# RADIO.net
KiCad netlist of a schematic drawn in Altium Designer
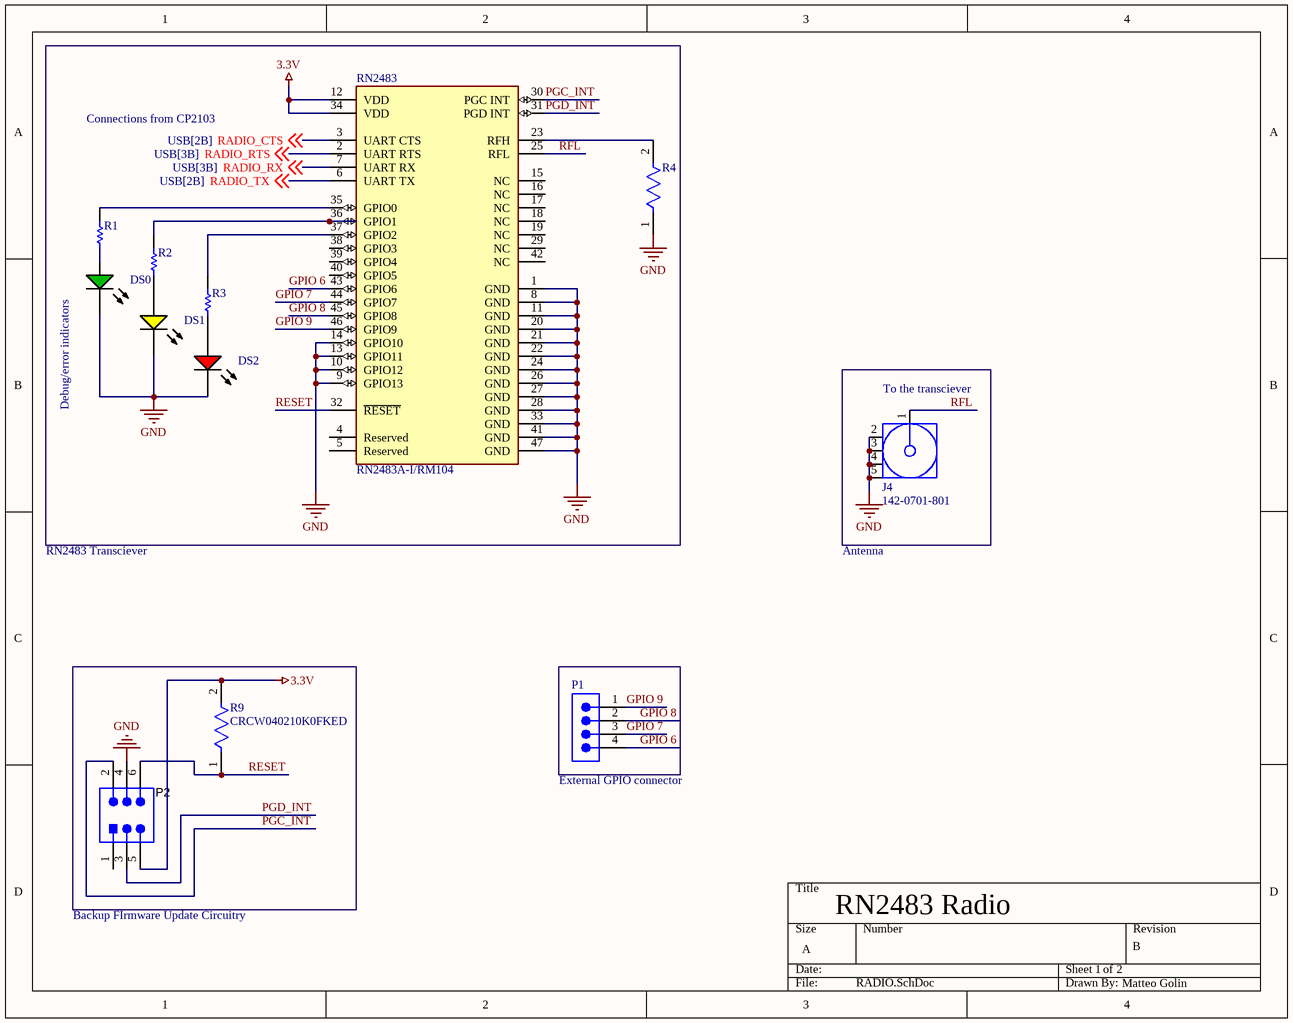
[diagram p0: RADIO.SchDoc]

(export (version "E")
  (design (tool "Eeschema 10.0.6"))
  (components
    (comp (ref "DS0")
      (value "HSMG-C190")
      (footprint "AVAG-HSMX-C190_V")
      (description "Chip LED, Green, 2.2 V, -40 to 85 degC, 2-Pin SMD, RoHS, Tape and Reel")
      (libsource (lib "Altium Content Vault") (part "LED-GREEN-AK-2"))
    )
    (comp (ref "DS1")
      (value "HSMY-C190")
      (footprint "AVAG-HSMX-C190_V")
      (description "LED Uni-Color Yellow, 65 mW, 20 mA, -40 to 85 degC, 2-Pin SMD, RoHS, Tape and Reel")
      (fields (field (name "TOLERANCE") "1%"))
      (libsource (lib "Altium Content Vault") (part "LED-YELLOW-AK-2"))
    )
    (comp (ref "DS2")
      (value "HSMH-C190")
      (footprint "AVAG-HSMX-C190_V")
      (description "LED Uni-Color Red, 65 mW, 20 mA, -40 to 85 degC, 2-Pin SMD, RoHS, Tape and Reel")
      (libsource (lib "Altium Content Vault") (part "LED-RED-AK-2"))
    )
    (comp (ref "J4")
      (value "142-0701-801")
      (footprint "CINC-142-0701-801_V")
      (description "SMA End Launch Jack Receptacle, 50 Ohm, 0 to 18 GHz, -65 to 165 degC, 5-Pin SMD, RoHS, Bulk")
      (fields (field (name "MANUFACTURER") "EmersonConnectivitySolutions"))
      (libsource (lib "Altium Content Vault") (part "CN-S-4F-RF5"))
    )
    (comp (ref "P1")
      (value "TSW-104-08-G-S")
      (footprint "SMTC-TSW-104-08-X-S")
      (description "0.025\" SQ Post Header, Through-hole, Vertical, -55 to 125 degC, 2.54 mm Pitch, 4-Pin, Male, RoHS")
      (fields (field (name "MANUFACTURER") "Samtec"))
      (libsource (lib "Altium Content Vault") (part "SMTC-TSW-104-08-X-S"))
    )
    (comp (ref "P2")
      (value "TSW-103-07-G-D")
      (footprint "SMTC-TSW-103-07-G-D_V")
      (fields (field (name "MANUFACTURER") "Samtec-Inc."))
      (libsource (lib "Altium Content Vault") (part "CN-2P-M-R6"))
    )
    (comp (ref "R1")
      (value "CRCW0402220KFKED")
      (footprint "RESC1005X40X25LL05T05")
      (fields (field (name "MANUFACTURER") "Vishay Dale"))
      (libsource (lib "Altium Content Vault") (part "RES"))
    )
    (comp (ref "R2")
      (value "CRCW0402220KFKED")
      (footprint "RESC1005X40X25LL05T05")
      (fields (field (name "MANUFACTURER") "Vishay Dale"))
      (libsource (lib "Altium Content Vault") (part "RES"))
    )
    (comp (ref "R3")
      (value "CRCW0402220KFKED")
      (footprint "RESC1005X40X25LL05T05")
      (fields (field (name "MANUFACTURER") "Vishay Dale"))
      (libsource (lib "Altium Content Vault") (part "RES"))
    )
    (comp (ref "R4")
      (value "CRCW060350R0FKEA")
      (footprint "FP-CRCW0603-e3-MFG")
      (description "RES Thick Film, 50Ω, 1%, 0.1W, 100ppm/°C, 0603")
      (fields (field (name "TOLERANCE") "1%"))
      (libsource (lib "Altium Content Vault") (part "1029c3af85768c4190bb7ad29bc67b5"))
    )
    (comp (ref "R9")
      (value "CRCW040210K0FKED")
      (footprint "FP-CRCW0402-e3-IPC_B")
      (description "RES SMD 10K OHM 1% 1/16W 0402")
      (fields (field (name "TOLERANCE") "1%"))
      (libsource (lib "Altium Content Vault") (part "1029c3af85768c4190bb7ad29bc67b5"))
    )
    (comp (ref "RN2483")
      (value "RN2483A-I/RM104")
      (footprint "FP-RN2483A-I-RM104-MFG")
      (fields
        (field (name "OCTOPART") "https://octopart.com/rn2483a-i%2Frm104-microchip-90584481")
        (field (name "MANUFACTURER") "Microchip")
      )
      (libsource (lib "Altium Content Vault") (part "630a5bff3a952dd521c0edb04079da7"))
    )
  )
  (nets
    (net (code "1") (name "/GPIO 6") (class "Default")
      (node (ref "P1") (pin "4") (pinfunction "4_4") (pintype "passive"))
      (node (ref "RN2483") (pin "43") (pinfunction "GPIO6_43") (pintype "bidirectional"))
    )
    (net (code "2") (name "/GPIO 7") (class "Default")
      (node (ref "P1") (pin "3") (pinfunction "3_3") (pintype "passive"))
      (node (ref "RN2483") (pin "44") (pinfunction "GPIO7_44") (pintype "bidirectional"))
    )
    (net (code "3") (name "/GPIO 8") (class "Default")
      (node (ref "P1") (pin "2") (pinfunction "2_2") (pintype "passive"))
      (node (ref "RN2483") (pin "45") (pinfunction "GPIO8_45") (pintype "bidirectional"))
    )
    (net (code "4") (name "/GPIO 9") (class "Default")
      (node (ref "P1") (pin "1") (pinfunction "1_1") (pintype "passive"))
      (node (ref "RN2483") (pin "46") (pinfunction "GPIO9_46") (pintype "bidirectional"))
    )
    (net (code "5") (name "/PGC_INT") (class "Default")
      (node (ref "P2") (pin "2") (pinfunction "2_2") (pintype "passive"))
      (node (ref "RN2483") (pin "30") (pinfunction "PGC_INT_30") (pintype "bidirectional"))
    )
    (net (code "6") (name "/PGD_INT") (class "Default")
      (node (ref "P2") (pin "3") (pinfunction "3_3") (pintype "passive"))
      (node (ref "RN2483") (pin "31") (pinfunction "PGD_INT_31") (pintype "bidirectional"))
    )
    (net (code "7") (name "/RESET") (class "Default")
      (node (ref "P2") (pin "6") (pinfunction "6_6") (pintype "passive"))
      (node (ref "R9") (pin "1") (pinfunction "1_1") (pintype "passive"))
      (node (ref "RN2483") (pin "32") (pinfunction "~{RESET}_32") (pintype "passive"))
    )
    (net (code "8") (name "/RFL") (class "Default")
      (node (ref "J4") (pin "1") (pinfunction "1_1") (pintype "passive"))
      (node (ref "RN2483") (pin "25") (pinfunction "RFL_25") (pintype "passive"))
    )
    (net (code "9") (name "3.3V") (class "Default")
      (node (ref "P2") (pin "5") (pinfunction "5_5") (pintype "passive"))
      (node (ref "R9") (pin "2") (pinfunction "2_2") (pintype "passive"))
      (node (ref "RN2483") (pin "12") (pinfunction "VDD_12") (pintype "passive"))
      (node (ref "RN2483") (pin "34") (pinfunction "VDD_34") (pintype "passive"))
    )
    (net (code "10") (name "GND") (class "Default")
      (node (ref "DS0") (pin "2") (pinfunction "K_2") (pintype "passive"))
      (node (ref "DS1") (pin "2") (pinfunction "K_2") (pintype "passive"))
      (node (ref "DS2") (pin "2") (pinfunction "K_2") (pintype "passive"))
      (node (ref "J4") (pin "2") (pinfunction "2_2") (pintype "passive"))
      (node (ref "J4") (pin "3") (pinfunction "3_3") (pintype "passive"))
      (node (ref "J4") (pin "4") (pinfunction "4_4") (pintype "passive"))
      (node (ref "J4") (pin "5") (pinfunction "5_5") (pintype "passive"))
      (node (ref "P2") (pin "4") (pinfunction "4_4") (pintype "passive"))
      (node (ref "R4") (pin "1") (pinfunction "1_1") (pintype "passive"))
      (node (ref "RN2483") (pin "1") (pinfunction "GND_1") (pintype "passive"))
      (node (ref "RN2483") (pin "10") (pinfunction "GPIO12_10") (pintype "bidirectional"))
      (node (ref "RN2483") (pin "11") (pinfunction "GND_11") (pintype "passive"))
      (node (ref "RN2483") (pin "13") (pinfunction "GPIO11_13") (pintype "bidirectional"))
      (node (ref "RN2483") (pin "14") (pinfunction "GPIO10_14") (pintype "bidirectional"))
      (node (ref "RN2483") (pin "20") (pinfunction "GND_20") (pintype "passive"))
      (node (ref "RN2483") (pin "21") (pinfunction "GND_21") (pintype "passive"))
      (node (ref "RN2483") (pin "22") (pinfunction "GND_22") (pintype "passive"))
      (node (ref "RN2483") (pin "24") (pinfunction "GND_24") (pintype "passive"))
      (node (ref "RN2483") (pin "26") (pinfunction "GND_26") (pintype "passive"))
      (node (ref "RN2483") (pin "27") (pinfunction "GND_27") (pintype "passive"))
      (node (ref "RN2483") (pin "28") (pinfunction "GND_28") (pintype "passive"))
      (node (ref "RN2483") (pin "33") (pinfunction "GND_33") (pintype "passive"))
      (node (ref "RN2483") (pin "41") (pinfunction "GND_41") (pintype "passive"))
      (node (ref "RN2483") (pin "47") (pinfunction "GND_47") (pintype "passive"))
      (node (ref "RN2483") (pin "8") (pinfunction "GND_8") (pintype "passive"))
      (node (ref "RN2483") (pin "9") (pinfunction "GPIO13_9") (pintype "bidirectional"))
    )
    (net (code "11") (name "Net-(DS0-A)") (class "Default")
      (node (ref "DS0") (pin "1") (pinfunction "A_1") (pintype "passive"))
      (node (ref "R1") (pin "1") (pinfunction "1_1") (pintype "passive"))
    )
    (net (code "12") (name "Net-(DS1-A)") (class "Default")
      (node (ref "DS1") (pin "1") (pinfunction "A_1") (pintype "passive"))
      (node (ref "R2") (pin "1") (pinfunction "1_1") (pintype "passive"))
    )
    (net (code "13") (name "Net-(DS2-A)") (class "Default")
      (node (ref "DS2") (pin "1") (pinfunction "A_1") (pintype "passive"))
      (node (ref "R3") (pin "1") (pinfunction "1_1") (pintype "passive"))
    )
    (net (code "14") (name "Net-(RN2483-GPIO0)") (class "Default")
      (node (ref "R1") (pin "2") (pinfunction "2_2") (pintype "passive"))
      (node (ref "RN2483") (pin "35") (pinfunction "GPIO0_35") (pintype "bidirectional"))
    )
    (net (code "15") (name "Net-(RN2483-GPIO1)") (class "Default")
      (node (ref "R2") (pin "2") (pinfunction "2_2") (pintype "passive"))
      (node (ref "RN2483") (pin "36") (pinfunction "GPIO1_36") (pintype "bidirectional"))
    )
    (net (code "16") (name "Net-(RN2483-GPIO2)") (class "Default")
      (node (ref "R3") (pin "2") (pinfunction "2_2") (pintype "passive"))
      (node (ref "RN2483") (pin "37") (pinfunction "GPIO2_37") (pintype "bidirectional"))
    )
    (net (code "17") (name "Net-(RN2483-RFH)") (class "Default")
      (node (ref "R4") (pin "2") (pinfunction "2_2") (pintype "passive"))
      (node (ref "RN2483") (pin "23") (pinfunction "RFH_23") (pintype "passive"))
    )
    (net (code "18") (name "RADIO_CTS") (class "Default")
      (node (ref "RN2483") (pin "3") (pinfunction "UART_CTS_3") (pintype "passive"))
    )
    (net (code "19") (name "RADIO_RTS") (class "Default")
      (node (ref "RN2483") (pin "2") (pinfunction "UART_RTS_2") (pintype "passive"))
    )
    (net (code "20") (name "RADIO_RX") (class "Default")
      (node (ref "RN2483") (pin "7") (pinfunction "UART_RX_7") (pintype "passive"))
    )
    (net (code "21") (name "RADIO_TX") (class "Default")
      (node (ref "RN2483") (pin "6") (pinfunction "UART_TX_6") (pintype "passive"))
    )
    (net (code "22") (name "unconnected-(P2-Pad1)") (class "Default")
      (node (ref "P2") (pin "1") (pinfunction "1_1") (pintype "passive"))
    )
    (net (code "23") (name "unconnected-(RN2483-GPIO3-Pad38)") (class "Default")
      (node (ref "RN2483") (pin "38") (pinfunction "GPIO3_38") (pintype "bidirectional"))
    )
    (net (code "24") (name "unconnected-(RN2483-GPIO4-Pad39)") (class "Default")
      (node (ref "RN2483") (pin "39") (pinfunction "GPIO4_39") (pintype "bidirectional"))
    )
    (net (code "25") (name "unconnected-(RN2483-GPIO5-Pad40)") (class "Default")
      (node (ref "RN2483") (pin "40") (pinfunction "GPIO5_40") (pintype "bidirectional"))
    )
    (net (code "26") (name "unconnected-(RN2483-NC-Pad15)") (class "Default")
      (node (ref "RN2483") (pin "15") (pinfunction "NC_15") (pintype "passive"))
    )
    (net (code "27") (name "unconnected-(RN2483-NC-Pad16)") (class "Default")
      (node (ref "RN2483") (pin "16") (pinfunction "NC_16") (pintype "passive"))
    )
    (net (code "28") (name "unconnected-(RN2483-NC-Pad17)") (class "Default")
      (node (ref "RN2483") (pin "17") (pinfunction "NC_17") (pintype "passive"))
    )
    (net (code "29") (name "unconnected-(RN2483-NC-Pad18)") (class "Default")
      (node (ref "RN2483") (pin "18") (pinfunction "NC_18") (pintype "passive"))
    )
    (net (code "30") (name "unconnected-(RN2483-NC-Pad19)") (class "Default")
      (node (ref "RN2483") (pin "19") (pinfunction "NC_19") (pintype "passive"))
    )
    (net (code "31") (name "unconnected-(RN2483-NC-Pad29)") (class "Default")
      (node (ref "RN2483") (pin "29") (pinfunction "NC_29") (pintype "passive"))
    )
    (net (code "32") (name "unconnected-(RN2483-NC-Pad42)") (class "Default")
      (node (ref "RN2483") (pin "42") (pinfunction "NC_42") (pintype "passive"))
    )
    (net (code "33") (name "unconnected-(RN2483-Reserved-Pad4)") (class "Default")
      (node (ref "RN2483") (pin "4") (pinfunction "Reserved_4") (pintype "passive"))
    )
    (net (code "34") (name "unconnected-(RN2483-Reserved-Pad5)") (class "Default")
      (node (ref "RN2483") (pin "5") (pinfunction "Reserved_5") (pintype "passive"))
    )
  )
)
